# Servo_control_board.net
KiCad netlist of a schematic drawn in Altium Designer
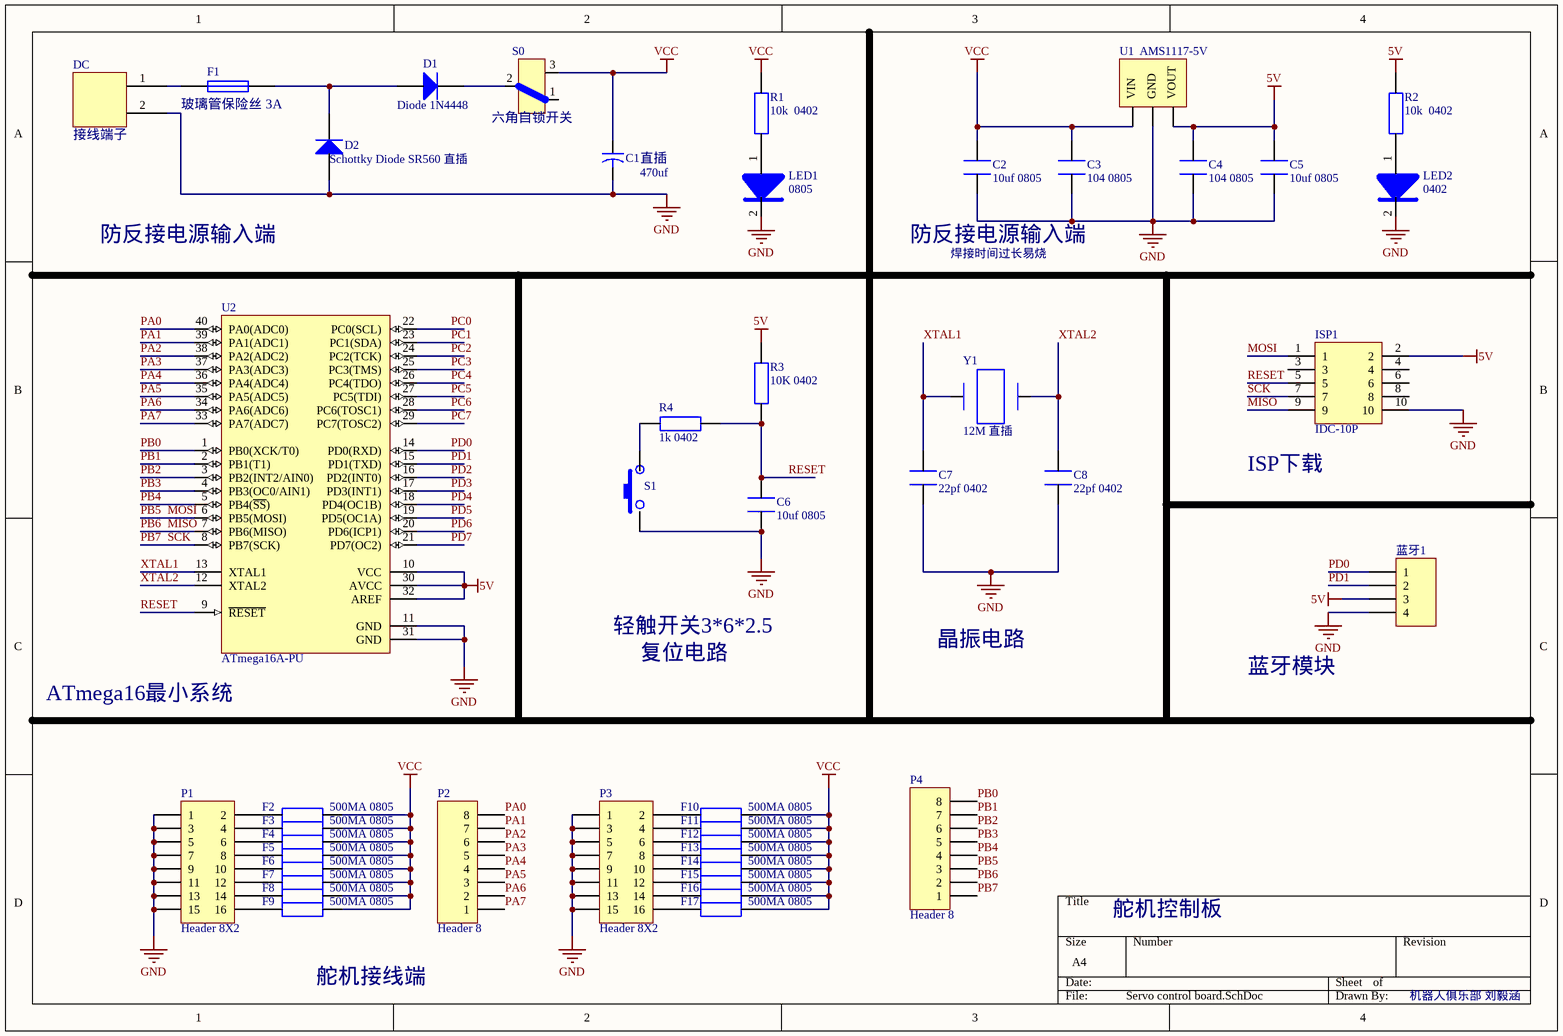
[diagram p0: Servo control board.SchDoc]

(export (version "E")
  (design (tool "Eeschema 10.0.6"))
  (components
    (comp (ref "C1")
      (value "直插")
      (footprint "CAPR5-4X5")
      (description "Capacitor")
      (fields (field (name "ALTIUM_VALUE") "470uf") (field (name "PUBLISHER") "Altium Limited"))
      (libsource (lib "原理图库") (part "Cap2"))
    )
    (comp (ref "C2") (value "10uf 0805") (footprint "0805_C") (libsource (lib "原理图库") (part "0805 C_1")))
    (comp (ref "C3") (value "104 0805") (footprint "0805_C") (libsource (lib "原理图库") (part "0805 C")))
    (comp (ref "C4") (value "104 0805") (footprint "0805_C") (libsource (lib "原理图库") (part "0805 C")))
    (comp (ref "C5") (value "10uf 0805") (footprint "0805_C") (libsource (lib "原理图库") (part "0805 C_1")))
    (comp (ref "C6") (value "10uf 0805") (footprint "0805_C") (libsource (lib "原理图库") (part "0805 C_1")))
    (comp (ref "C7") (value "22pf 0402") (footprint "0805_C") (libsource (lib "原理图库") (part "0805 C_2")))
    (comp (ref "C8") (value "22pf 0402") (footprint "0805_C") (libsource (lib "原理图库") (part "0805 C_2")))
    (comp (ref "D1")
      (value "Diode 1N4448")
      (footprint "DO-35")
      (description "High Conductance Fast Diode")
      (libsource (lib "原理图库") (part "Diode 1N4448"))
    )
    (comp (ref "D2")
      (value "Schottky Diode SR560 直插")
      (footprint "DO-35")
      (description "High Conductance Fast Diode")
      (libsource (lib "原理图库") (part "Diode 1N4448_1"))
    )
    (comp (ref "DC") (value "接线端子") (footprint "接线端子-仅空") (libsource (lib "原理图库") (part "接线端子")))
    (comp (ref "F1")
      (value "玻璃管保险丝 3A")
      (footprint "PIN-W2/E2.8")
      (description "Fuse")
      (fields (field (name "PUBLISHER") "Altium Limited"))
      (libsource (lib "原理图库") (part "Fuse 1"))
    )
    (comp (ref "F2") (value "500MA 0805") (footprint "0805_R") (libsource (lib "原理图库") (part "0805 R_2")))
    (comp (ref "F3") (value "500MA 0805") (footprint "0805_R") (libsource (lib "原理图库") (part "0805 R_2")))
    (comp (ref "F4") (value "500MA 0805") (footprint "0805_R") (libsource (lib "原理图库") (part "0805 R_2")))
    (comp (ref "F5") (value "500MA 0805") (footprint "0805_R") (libsource (lib "原理图库") (part "0805 R_2")))
    (comp (ref "F6") (value "500MA 0805") (footprint "0805_R") (libsource (lib "原理图库") (part "0805 R_2")))
    (comp (ref "F7") (value "500MA 0805") (footprint "0805_R") (libsource (lib "原理图库") (part "0805 R_2")))
    (comp (ref "F8") (value "500MA 0805") (footprint "0805_R") (libsource (lib "原理图库") (part "0805 R_2")))
    (comp (ref "F9") (value "500MA 0805") (footprint "0805_R") (libsource (lib "原理图库") (part "0805 R_2")))
    (comp (ref "F10") (value "500MA 0805") (footprint "0805_R") (libsource (lib "原理图库") (part "0805 R_2")))
    (comp (ref "F11") (value "500MA 0805") (footprint "0805_R") (libsource (lib "原理图库") (part "0805 R_2")))
    (comp (ref "F12") (value "500MA 0805") (footprint "0805_R") (libsource (lib "原理图库") (part "0805 R_2")))
    (comp (ref "F13") (value "500MA 0805") (footprint "0805_R") (libsource (lib "原理图库") (part "0805 R_2")))
    (comp (ref "F14") (value "500MA 0805") (footprint "0805_R") (libsource (lib "原理图库") (part "0805 R_2")))
    (comp (ref "F15") (value "500MA 0805") (footprint "0805_R") (libsource (lib "原理图库") (part "0805 R_2")))
    (comp (ref "F16") (value "500MA 0805") (footprint "0805_R") (libsource (lib "原理图库") (part "0805 R_2")))
    (comp (ref "F17") (value "500MA 0805") (footprint "0805_R") (libsource (lib "原理图库") (part "0805 R_2")))
    (comp (ref "ISP1") (value "IDC-10P") (footprint "IDC2.54-10P") (libsource (lib "原理图库") (part "IDC-10P")))
    (comp (ref "LED1") (value "0805") (footprint "LED贴片") (libsource (lib "原理图库") (part "LED贴片")))
    (comp (ref "LED2") (value "0402") (footprint "LED贴片") (libsource (lib "原理图库") (part "LED贴片")))
    (comp (ref "P1")
      (value "Header 8X2")
      (footprint "HDR2X8")
      (description "Header, 8-Pin, Dual row")
      (fields (field (name "PUBLISHER") "Altium Limited"))
      (libsource (lib "原理图库") (part "Header 8X2"))
    )
    (comp (ref "P2")
      (value "Header 8")
      (footprint "HDR1X8")
      (description "Header, 8-Pin")
      (fields (field (name "PUBLISHER") "Altium Limited"))
      (libsource (lib "原理图库") (part "Header 8"))
    )
    (comp (ref "P3")
      (value "Header 8X2")
      (footprint "HDR2X8")
      (description "Header, 8-Pin, Dual row")
      (fields (field (name "PUBLISHER") "Altium Limited"))
      (libsource (lib "原理图库") (part "Header 8X2"))
    )
    (comp (ref "P4")
      (value "Header 8")
      (footprint "HDR1X8")
      (description "Header, 8-Pin")
      (fields (field (name "PUBLISHER") "Altium Limited"))
      (libsource (lib "原理图库") (part "Header 8"))
    )
    (comp (ref "R1") (value "10k  0402") (footprint "0805_R") (libsource (lib "原理图库") (part "0805 R")))
    (comp (ref "R2") (value "10k  0402") (footprint "0805_R") (libsource (lib "原理图库") (part "0805 R")))
    (comp (ref "R3") (value "10K 0402") (footprint "0805_R") (libsource (lib "原理图库") (part "0805 R_1")))
    (comp (ref "R4") (value "1k 0402") (footprint "0805_R") (libsource (lib "原理图库") (part "0805 R_1")))
    (comp (ref "S0") (value "六角自锁开关") (footprint "DPDT-6") (libsource (lib "原理图库") (part "六脚自锁开关")))
    (comp (ref "S1")
      (value "轻触开关（3*6*2.5mm）")
      (footprint "轻触开关（3*6*2.5mm）")
      (libsource (lib "原理图库") (part "轻触开关（3*6*2.5mm）"))
    )
    (comp (ref "U1") (value "AMS1117-5V") (footprint "AMS1117") (libsource (lib "原理图库") (part "AMS1117")))
    (comp (ref "U2") (value "ATmega16A-PU") (footprint "40P6") (libsource (lib "原理图库") (part "ATmega16A-PU")))
    (comp (ref "Y1") (value "12M 直插") (footprint "晶振") (libsource (lib "原理图库") (part "晶振")))
    (comp (ref "蓝牙1")
      (value "Header 4")
      (footprint "HDR1X4")
      (description "Header, 4-Pin")
      (fields (field (name "PUBLISHER") "Altium Limited"))
      (libsource (lib "原理图库") (part "Header 4"))
    )
  )
  (nets
    (net (code "1") (name "/MISO") (class "Default")
      (node (ref "ISP1") (pin "9") (pinfunction "9_9") (pintype "passive"))
      (node (ref "P4") (pin "2") (pinfunction "2_2") (pintype "passive"))
      (node (ref "U2") (pin "7") (pinfunction "PB6(MISO)_7") (pintype "bidirectional"))
    )
    (net (code "2") (name "/MOSI") (class "Default")
      (node (ref "ISP1") (pin "1") (pinfunction "1_1") (pintype "passive"))
      (node (ref "P4") (pin "3") (pinfunction "3_3") (pintype "passive"))
      (node (ref "U2") (pin "6") (pinfunction "PB5(MOSI)_6") (pintype "bidirectional"))
    )
    (net (code "3") (name "/PA0") (class "Default")
      (node (ref "P2") (pin "8") (pinfunction "8_8") (pintype "passive"))
      (node (ref "U2") (pin "40") (pinfunction "PA0(ADC0)_40") (pintype "bidirectional"))
    )
    (net (code "4") (name "/PA1") (class "Default")
      (node (ref "P2") (pin "7") (pinfunction "7_7") (pintype "passive"))
      (node (ref "U2") (pin "39") (pinfunction "PA1(ADC1)_39") (pintype "bidirectional"))
    )
    (net (code "5") (name "/PA2") (class "Default")
      (node (ref "P2") (pin "6") (pinfunction "6_6") (pintype "passive"))
      (node (ref "U2") (pin "38") (pinfunction "PA2(ADC2)_38") (pintype "bidirectional"))
    )
    (net (code "6") (name "/PA3") (class "Default")
      (node (ref "P2") (pin "5") (pinfunction "5_5") (pintype "passive"))
      (node (ref "U2") (pin "37") (pinfunction "PA3(ADC3)_37") (pintype "bidirectional"))
    )
    (net (code "7") (name "/PA4") (class "Default")
      (node (ref "P2") (pin "4") (pinfunction "4_4") (pintype "passive"))
      (node (ref "U2") (pin "36") (pinfunction "PA4(ADC4)_36") (pintype "bidirectional"))
    )
    (net (code "8") (name "/PA5") (class "Default")
      (node (ref "P2") (pin "3") (pinfunction "3_3") (pintype "passive"))
      (node (ref "U2") (pin "35") (pinfunction "PA5(ADC5)_35") (pintype "bidirectional"))
    )
    (net (code "9") (name "/PA6") (class "Default")
      (node (ref "P2") (pin "2") (pinfunction "2_2") (pintype "passive"))
      (node (ref "U2") (pin "34") (pinfunction "PA6(ADC6)_34") (pintype "bidirectional"))
    )
    (net (code "10") (name "/PA7") (class "Default")
      (node (ref "P2") (pin "1") (pinfunction "1_1") (pintype "passive"))
      (node (ref "U2") (pin "33") (pinfunction "PA7(ADC7)_33") (pintype "bidirectional"))
    )
    (net (code "11") (name "/PB0") (class "Default")
      (node (ref "P4") (pin "8") (pinfunction "8_8") (pintype "passive"))
      (node (ref "U2") (pin "1") (pinfunction "PB0(XCK/T0)_1") (pintype "bidirectional"))
    )
    (net (code "12") (name "/PB1") (class "Default")
      (node (ref "P4") (pin "7") (pinfunction "7_7") (pintype "passive"))
      (node (ref "U2") (pin "2") (pinfunction "PB1(T1)_2") (pintype "bidirectional"))
    )
    (net (code "13") (name "/PB2") (class "Default")
      (node (ref "P4") (pin "6") (pinfunction "6_6") (pintype "passive"))
      (node (ref "U2") (pin "3") (pinfunction "PB2(INT2/AIN0)_3") (pintype "bidirectional"))
    )
    (net (code "14") (name "/PB3") (class "Default")
      (node (ref "P4") (pin "5") (pinfunction "5_5") (pintype "passive"))
      (node (ref "U2") (pin "4") (pinfunction "PB3(OC0/AIN1)_4") (pintype "bidirectional"))
    )
    (net (code "15") (name "/PB4") (class "Default")
      (node (ref "P4") (pin "4") (pinfunction "4_4") (pintype "passive"))
      (node (ref "U2") (pin "5") (pinfunction "PB4(~{SS})_5") (pintype "bidirectional"))
    )
    (net (code "16") (name "/PB7") (class "Default")
      (node (ref "ISP1") (pin "7") (pinfunction "7_7") (pintype "passive"))
      (node (ref "P4") (pin "1") (pinfunction "1_1") (pintype "passive"))
      (node (ref "U2") (pin "8") (pinfunction "PB7(SCK)_8") (pintype "bidirectional"))
    )
    (net (code "17") (name "/PC0") (class "Default")
      (node (ref "U2") (pin "22") (pinfunction "PC0(SCL)_22") (pintype "bidirectional"))
    )
    (net (code "18") (name "/PC1") (class "Default")
      (node (ref "U2") (pin "23") (pinfunction "PC1(SDA)_23") (pintype "bidirectional"))
    )
    (net (code "19") (name "/PC2") (class "Default")
      (node (ref "U2") (pin "24") (pinfunction "PC2(TCK)_24") (pintype "bidirectional"))
    )
    (net (code "20") (name "/PC3") (class "Default")
      (node (ref "U2") (pin "25") (pinfunction "PC3(TMS)_25") (pintype "bidirectional"))
    )
    (net (code "21") (name "/PC4") (class "Default")
      (node (ref "U2") (pin "26") (pinfunction "PC4(TDO)_26") (pintype "bidirectional"))
    )
    (net (code "22") (name "/PC5") (class "Default")
      (node (ref "U2") (pin "27") (pinfunction "PC5(TDI)_27") (pintype "bidirectional"))
    )
    (net (code "23") (name "/PC6") (class "Default")
      (node (ref "U2") (pin "28") (pinfunction "PC6(TOSC1)_28") (pintype "bidirectional"))
    )
    (net (code "24") (name "/PC7") (class "Default")
      (node (ref "U2") (pin "29") (pinfunction "PC7(TOSC2)_29") (pintype "bidirectional"))
    )
    (net (code "25") (name "/PD0") (class "Default")
      (node (ref "U2") (pin "14") (pinfunction "PD0(RXD)_14") (pintype "bidirectional"))
      (node (ref "蓝牙1") (pin "1") (pinfunction "1_1") (pintype "passive"))
    )
    (net (code "26") (name "/PD1") (class "Default")
      (node (ref "U2") (pin "15") (pinfunction "PD1(TXD)_15") (pintype "bidirectional"))
      (node (ref "蓝牙1") (pin "2") (pinfunction "2_2") (pintype "passive"))
    )
    (net (code "27") (name "/PD2") (class "Default")
      (node (ref "U2") (pin "16") (pinfunction "PD2(INT0)_16") (pintype "bidirectional"))
    )
    (net (code "28") (name "/PD3") (class "Default")
      (node (ref "U2") (pin "17") (pinfunction "PD3(INT1)_17") (pintype "bidirectional"))
    )
    (net (code "29") (name "/PD4") (class "Default")
      (node (ref "U2") (pin "18") (pinfunction "PD4(OC1B)_18") (pintype "bidirectional"))
    )
    (net (code "30") (name "/PD5") (class "Default")
      (node (ref "U2") (pin "19") (pinfunction "PD5(OC1A)_19") (pintype "bidirectional"))
    )
    (net (code "31") (name "/PD6") (class "Default")
      (node (ref "U2") (pin "20") (pinfunction "PD6(ICP1)_20") (pintype "bidirectional"))
    )
    (net (code "32") (name "/PD7") (class "Default")
      (node (ref "U2") (pin "21") (pinfunction "PD7(OC2)_21") (pintype "bidirectional"))
    )
    (net (code "33") (name "/RESET") (class "Default")
      (node (ref "C6") (pin "2") (pinfunction "2_2") (pintype "passive"))
      (node (ref "ISP1") (pin "5") (pinfunction "5_5") (pintype "passive"))
      (node (ref "R3") (pin "1") (pinfunction "1_1") (pintype "passive"))
      (node (ref "R4") (pin "2") (pinfunction "2_2") (pintype "passive"))
      (node (ref "U2") (pin "9") (pinfunction "~{RESET}_9") (pintype "input"))
    )
    (net (code "34") (name "/XTAL1") (class "Default")
      (node (ref "C7") (pin "2") (pinfunction "2_2") (pintype "passive"))
      (node (ref "U2") (pin "13") (pinfunction "XTAL1_13") (pintype "passive"))
      (node (ref "Y1") (pin "2") (pinfunction "2_2") (pintype "passive"))
    )
    (net (code "35") (name "/XTAL2") (class "Default")
      (node (ref "C8") (pin "2") (pinfunction "2_2") (pintype "passive"))
      (node (ref "U2") (pin "12") (pinfunction "XTAL2_12") (pintype "passive"))
      (node (ref "Y1") (pin "1") (pinfunction "1_1") (pintype "passive"))
    )
    (net (code "36") (name "5V") (class "Default")
      (node (ref "C4") (pin "2") (pinfunction "2_2") (pintype "passive"))
      (node (ref "C5") (pin "2") (pinfunction "2_2") (pintype "passive"))
      (node (ref "ISP1") (pin "2") (pinfunction "2_2") (pintype "passive"))
      (node (ref "R2") (pin "2") (pinfunction "2_2") (pintype "passive"))
      (node (ref "R3") (pin "2") (pinfunction "2_2") (pintype "passive"))
      (node (ref "U1") (pin "3") (pinfunction "3_3") (pintype "passive"))
      (node (ref "U2") (pin "10") (pinfunction "VCC_10") (pintype "power_in"))
      (node (ref "U2") (pin "30") (pinfunction "AVCC_30") (pintype "power_in"))
      (node (ref "U2") (pin "32") (pinfunction "AREF_32") (pintype "power_in"))
      (node (ref "蓝牙1") (pin "3") (pinfunction "3_3") (pintype "passive"))
    )
    (net (code "37") (name "GND") (class "Default")
      (node (ref "C1") (pin "2") (pinfunction "2_2") (pintype "passive"))
      (node (ref "C2") (pin "1") (pinfunction "1_1") (pintype "passive"))
      (node (ref "C3") (pin "1") (pinfunction "1_1") (pintype "passive"))
      (node (ref "C4") (pin "1") (pinfunction "1_1") (pintype "passive"))
      (node (ref "C5") (pin "1") (pinfunction "1_1") (pintype "passive"))
      (node (ref "C6") (pin "1") (pinfunction "1_1") (pintype "passive"))
      (node (ref "C7") (pin "1") (pinfunction "1_1") (pintype "passive"))
      (node (ref "C8") (pin "1") (pinfunction "1_1") (pintype "passive"))
      (node (ref "D2") (pin "1") (pinfunction "A_1") (pintype "passive"))
      (node (ref "DC") (pin "2") (pintype "passive"))
      (node (ref "ISP1") (pin "10") (pinfunction "10_10") (pintype "passive"))
      (node (ref "LED1") (pin "2") (pinfunction "2_2") (pintype "passive"))
      (node (ref "LED2") (pin "2") (pinfunction "2_2") (pintype "passive"))
      (node (ref "P1") (pin "1") (pinfunction "1_1") (pintype "passive"))
      (node (ref "P1") (pin "11") (pinfunction "11_11") (pintype "passive"))
      (node (ref "P1") (pin "13") (pinfunction "13_13") (pintype "passive"))
      (node (ref "P1") (pin "15") (pinfunction "15_15") (pintype "passive"))
      (node (ref "P1") (pin "3") (pinfunction "3_3") (pintype "passive"))
      (node (ref "P1") (pin "5") (pinfunction "5_5") (pintype "passive"))
      (node (ref "P1") (pin "7") (pinfunction "7_7") (pintype "passive"))
      (node (ref "P1") (pin "9") (pinfunction "9_9") (pintype "passive"))
      (node (ref "P3") (pin "1") (pinfunction "1_1") (pintype "passive"))
      (node (ref "P3") (pin "11") (pinfunction "11_11") (pintype "passive"))
      (node (ref "P3") (pin "13") (pinfunction "13_13") (pintype "passive"))
      (node (ref "P3") (pin "15") (pinfunction "15_15") (pintype "passive"))
      (node (ref "P3") (pin "3") (pinfunction "3_3") (pintype "passive"))
      (node (ref "P3") (pin "5") (pinfunction "5_5") (pintype "passive"))
      (node (ref "P3") (pin "7") (pinfunction "7_7") (pintype "passive"))
      (node (ref "P3") (pin "9") (pinfunction "9_9") (pintype "passive"))
      (node (ref "S1") (pin "1") (pinfunction "1_1") (pintype "passive"))
      (node (ref "U1") (pin "2") (pinfunction "2_2") (pintype "passive"))
      (node (ref "U2") (pin "11") (pinfunction "GND_11") (pintype "power_in"))
      (node (ref "U2") (pin "31") (pinfunction "GND_31") (pintype "power_in"))
      (node (ref "蓝牙1") (pin "4") (pinfunction "4_4") (pintype "passive"))
    )
    (net (code "38") (name "Net-(D1-A)") (class "Default")
      (node (ref "D1") (pin "1") (pinfunction "A_1") (pintype "passive"))
      (node (ref "D2") (pin "2") (pinfunction "K_2") (pintype "passive"))
      (node (ref "F1") (pin "2") (pinfunction "2_2") (pintype "passive"))
    )
    (net (code "39") (name "Net-(D1-K)") (class "Default")
      (node (ref "D1") (pin "2") (pinfunction "K_2") (pintype "passive"))
      (node (ref "S0") (pin "2") (pinfunction "2_2") (pintype "passive"))
    )
    (net (code "40") (name "Net-(DC-Pad1)") (class "Default")
      (node (ref "DC") (pin "1") (pintype "passive"))
      (node (ref "F1") (pin "1") (pinfunction "1_1") (pintype "passive"))
    )
    (net (code "41") (name "Net-(F2-Pad1)") (class "Default")
      (node (ref "F2") (pin "1") (pinfunction "1_1") (pintype "passive"))
      (node (ref "P1") (pin "2") (pinfunction "2_2") (pintype "passive"))
    )
    (net (code "42") (name "Net-(F3-Pad1)") (class "Default")
      (node (ref "F3") (pin "1") (pinfunction "1_1") (pintype "passive"))
      (node (ref "P1") (pin "4") (pinfunction "4_4") (pintype "passive"))
    )
    (net (code "43") (name "Net-(F4-Pad1)") (class "Default")
      (node (ref "F4") (pin "1") (pinfunction "1_1") (pintype "passive"))
      (node (ref "P1") (pin "6") (pinfunction "6_6") (pintype "passive"))
    )
    (net (code "44") (name "Net-(F5-Pad1)") (class "Default")
      (node (ref "F5") (pin "1") (pinfunction "1_1") (pintype "passive"))
      (node (ref "P1") (pin "8") (pinfunction "8_8") (pintype "passive"))
    )
    (net (code "45") (name "Net-(F6-Pad1)") (class "Default")
      (node (ref "F6") (pin "1") (pinfunction "1_1") (pintype "passive"))
      (node (ref "P1") (pin "10") (pinfunction "10_10") (pintype "passive"))
    )
    (net (code "46") (name "Net-(F7-Pad1)") (class "Default")
      (node (ref "F7") (pin "1") (pinfunction "1_1") (pintype "passive"))
      (node (ref "P1") (pin "12") (pinfunction "12_12") (pintype "passive"))
    )
    (net (code "47") (name "Net-(F8-Pad1)") (class "Default")
      (node (ref "F8") (pin "1") (pinfunction "1_1") (pintype "passive"))
      (node (ref "P1") (pin "14") (pinfunction "14_14") (pintype "passive"))
    )
    (net (code "48") (name "Net-(F9-Pad1)") (class "Default")
      (node (ref "F9") (pin "1") (pinfunction "1_1") (pintype "passive"))
      (node (ref "P1") (pin "16") (pinfunction "16_16") (pintype "passive"))
    )
    (net (code "49") (name "Net-(F10-Pad1)") (class "Default")
      (node (ref "F10") (pin "1") (pinfunction "1_1") (pintype "passive"))
      (node (ref "P3") (pin "2") (pinfunction "2_2") (pintype "passive"))
    )
    (net (code "50") (name "Net-(F11-Pad1)") (class "Default")
      (node (ref "F11") (pin "1") (pinfunction "1_1") (pintype "passive"))
      (node (ref "P3") (pin "4") (pinfunction "4_4") (pintype "passive"))
    )
    (net (code "51") (name "Net-(F12-Pad1)") (class "Default")
      (node (ref "F12") (pin "1") (pinfunction "1_1") (pintype "passive"))
      (node (ref "P3") (pin "6") (pinfunction "6_6") (pintype "passive"))
    )
    (net (code "52") (name "Net-(F13-Pad1)") (class "Default")
      (node (ref "F13") (pin "1") (pinfunction "1_1") (pintype "passive"))
      (node (ref "P3") (pin "8") (pinfunction "8_8") (pintype "passive"))
    )
    (net (code "53") (name "Net-(F14-Pad1)") (class "Default")
      (node (ref "F14") (pin "1") (pinfunction "1_1") (pintype "passive"))
      (node (ref "P3") (pin "10") (pinfunction "10_10") (pintype "passive"))
    )
    (net (code "54") (name "Net-(F15-Pad1)") (class "Default")
      (node (ref "F15") (pin "1") (pinfunction "1_1") (pintype "passive"))
      (node (ref "P3") (pin "12") (pinfunction "12_12") (pintype "passive"))
    )
    (net (code "55") (name "Net-(F16-Pad1)") (class "Default")
      (node (ref "F16") (pin "1") (pinfunction "1_1") (pintype "passive"))
      (node (ref "P3") (pin "14") (pinfunction "14_14") (pintype "passive"))
    )
    (net (code "56") (name "Net-(F17-Pad1)") (class "Default")
      (node (ref "F17") (pin "1") (pinfunction "1_1") (pintype "passive"))
      (node (ref "P3") (pin "16") (pinfunction "16_16") (pintype "passive"))
    )
    (net (code "57") (name "Net-(LED1-Pad1)") (class "Default")
      (node (ref "LED1") (pin "1") (pinfunction "1_1") (pintype "passive"))
      (node (ref "R1") (pin "1") (pinfunction "1_1") (pintype "passive"))
    )
    (net (code "58") (name "Net-(LED2-Pad1)") (class "Default")
      (node (ref "LED2") (pin "1") (pinfunction "1_1") (pintype "passive"))
      (node (ref "R2") (pin "1") (pinfunction "1_1") (pintype "passive"))
    )
    (net (code "59") (name "Net-(R4-Pad1)") (class "Default")
      (node (ref "R4") (pin "1") (pinfunction "1_1") (pintype "passive"))
      (node (ref "S1") (pin "2") (pinfunction "2_2") (pintype "passive"))
    )
    (net (code "60") (name "VCC") (class "Default")
      (node (ref "C1") (pin "1") (pinfunction "1_1") (pintype "passive"))
      (node (ref "C2") (pin "2") (pinfunction "2_2") (pintype "passive"))
      (node (ref "C3") (pin "2") (pinfunction "2_2") (pintype "passive"))
      (node (ref "F10") (pin "2") (pinfunction "2_2") (pintype "passive"))
      (node (ref "F11") (pin "2") (pinfunction "2_2") (pintype "passive"))
      (node (ref "F12") (pin "2") (pinfunction "2_2") (pintype "passive"))
      (node (ref "F13") (pin "2") (pinfunction "2_2") (pintype "passive"))
      (node (ref "F14") (pin "2") (pinfunction "2_2") (pintype "passive"))
      (node (ref "F15") (pin "2") (pinfunction "2_2") (pintype "passive"))
      (node (ref "F16") (pin "2") (pinfunction "2_2") (pintype "passive"))
      (node (ref "F17") (pin "2") (pinfunction "2_2") (pintype "passive"))
      (node (ref "F2") (pin "2") (pinfunction "2_2") (pintype "passive"))
      (node (ref "F3") (pin "2") (pinfunction "2_2") (pintype "passive"))
      (node (ref "F4") (pin "2") (pinfunction "2_2") (pintype "passive"))
      (node (ref "F5") (pin "2") (pinfunction "2_2") (pintype "passive"))
      (node (ref "F6") (pin "2") (pinfunction "2_2") (pintype "passive"))
      (node (ref "F7") (pin "2") (pinfunction "2_2") (pintype "passive"))
      (node (ref "F8") (pin "2") (pinfunction "2_2") (pintype "passive"))
      (node (ref "F9") (pin "2") (pinfunction "2_2") (pintype "passive"))
      (node (ref "R1") (pin "2") (pinfunction "2_2") (pintype "passive"))
      (node (ref "S0") (pin "3") (pinfunction "3_3") (pintype "passive"))
      (node (ref "U1") (pin "1") (pinfunction "1_1") (pintype "passive"))
    )
    (net (code "61") (name "unconnected-(ISP1-Pad3)") (class "Default")
      (node (ref "ISP1") (pin "3") (pinfunction "3_3") (pintype "passive"))
    )
    (net (code "62") (name "unconnected-(ISP1-Pad4)") (class "Default")
      (node (ref "ISP1") (pin "4") (pinfunction "4_4") (pintype "passive"))
    )
    (net (code "63") (name "unconnected-(ISP1-Pad6)") (class "Default")
      (node (ref "ISP1") (pin "6") (pinfunction "6_6") (pintype "passive"))
    )
    (net (code "64") (name "unconnected-(ISP1-Pad8)") (class "Default")
      (node (ref "ISP1") (pin "8") (pinfunction "8_8") (pintype "passive"))
    )
    (net (code "65") (name "unconnected-(S0-Pad1)") (class "Default")
      (node (ref "S0") (pin "1") (pinfunction "1_1") (pintype "passive"))
    )
    (net (code "66") (name "unconnected-(S0-Pad4)") (class "Default")
      (node (ref "S0") (pin "4") (pinfunction "4_4") (pintype "passive"))
    )
    (net (code "67") (name "unconnected-(S0-Pad5)") (class "Default")
      (node (ref "S0") (pin "5") (pinfunction "5_5") (pintype "passive"))
    )
    (net (code "68") (name "unconnected-(S0-Pad6)") (class "Default")
      (node (ref "S0") (pin "6") (pinfunction "6_6") (pintype "passive"))
    )
  )
)
